# VoltageSourcePCB.net
KiCad netlist of a schematic drawn in EAGLE
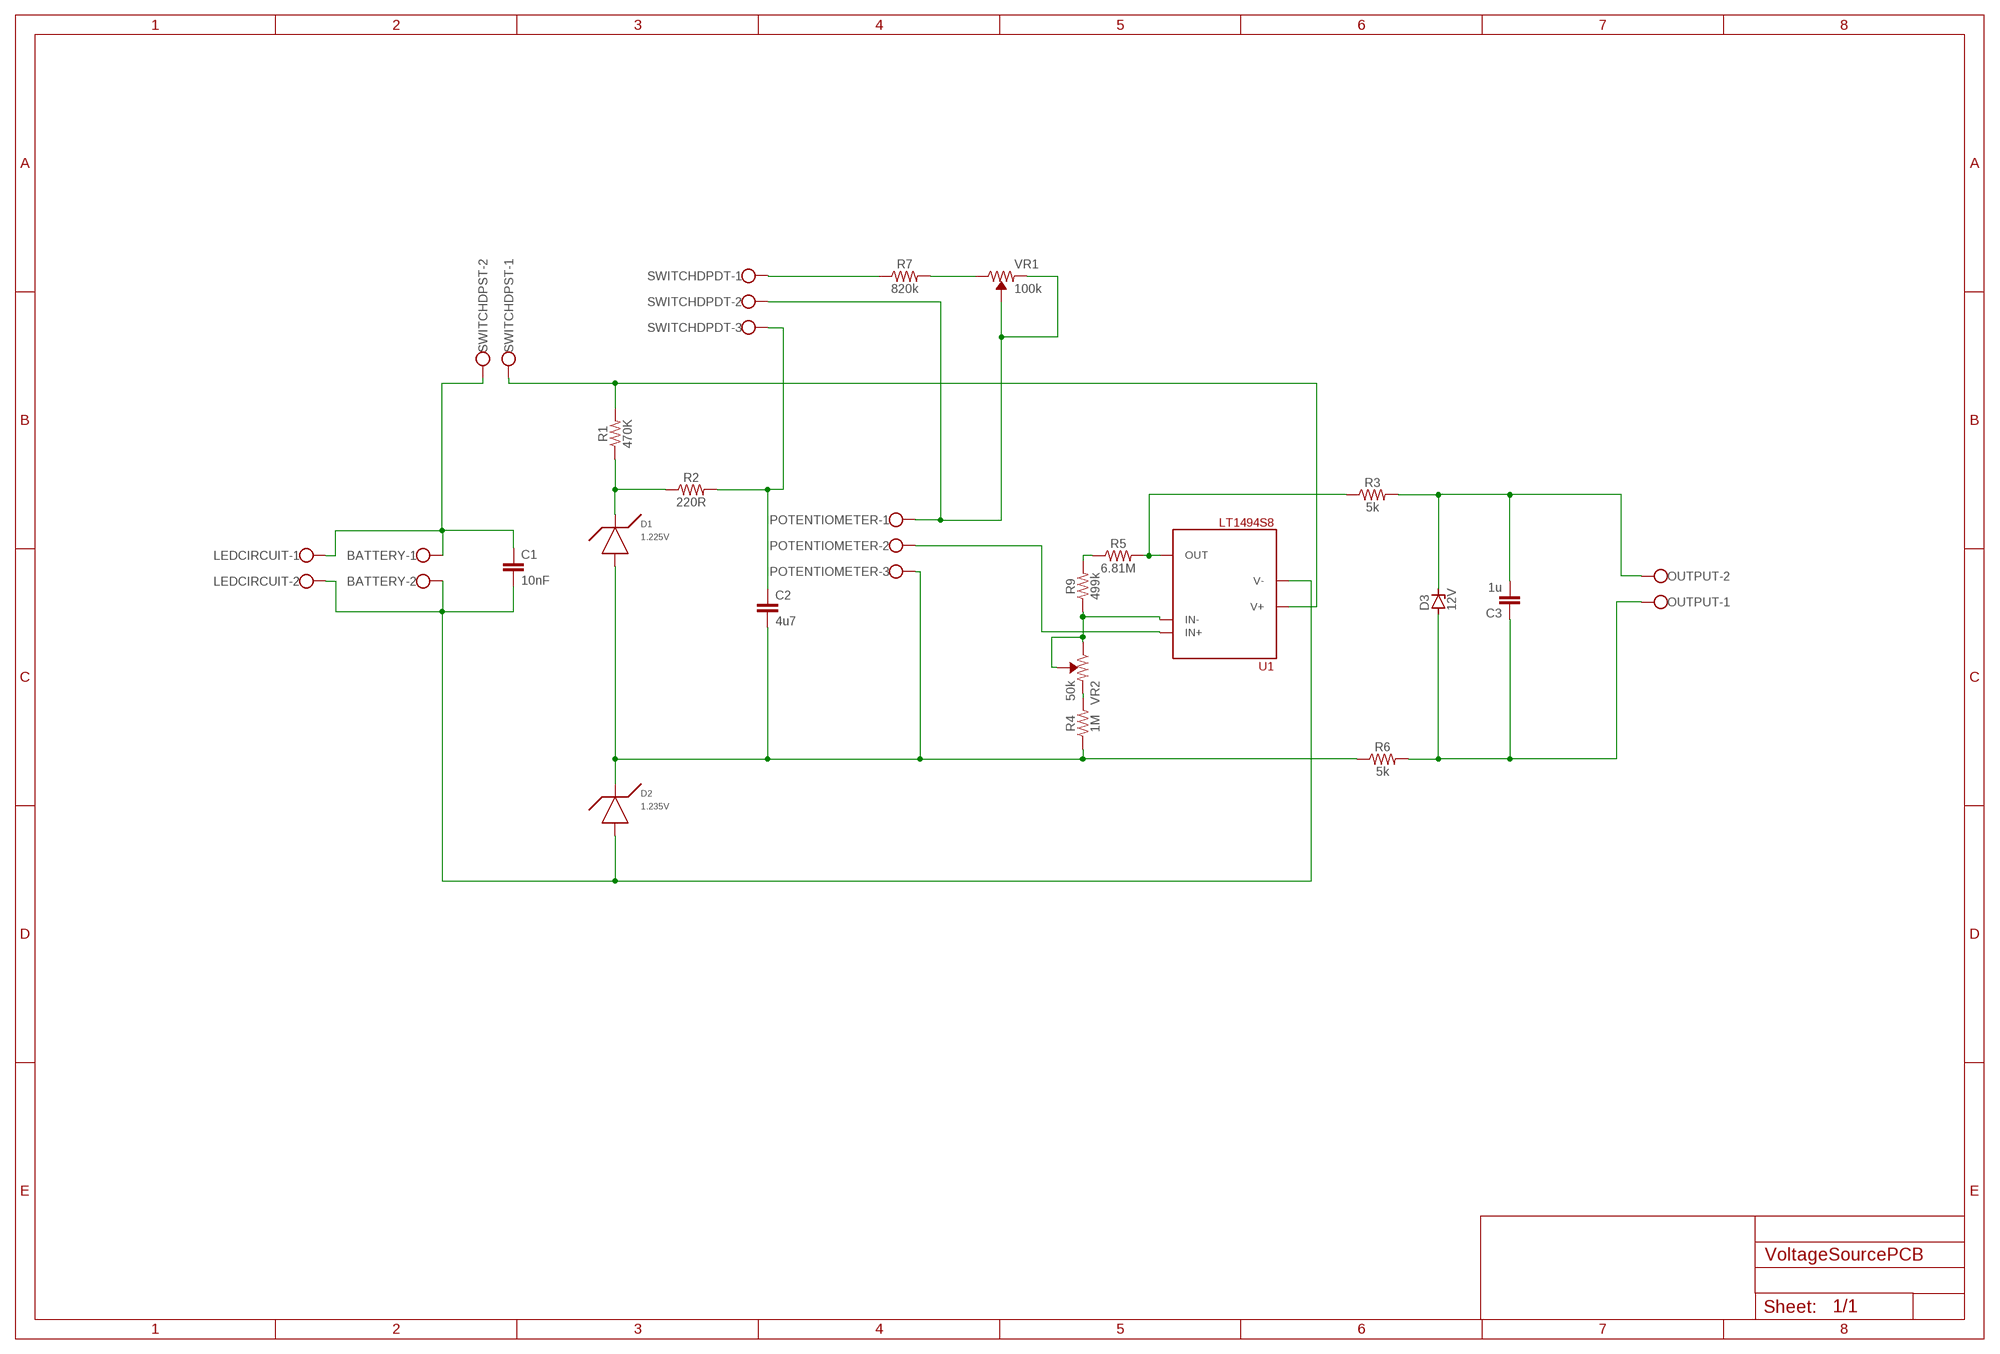
[diagram p0: schematic, sheet 1]

(export (version "E")
  (design (tool "Eeschema 10.0.6"))
  (components
    (comp (ref "BATTERY")
      (value "W237-102")
      (footprint "eagle-import:W237-102")
      (fields (field (name "MPN") "237-102"))
      (libsource (lib "eagle-import") (part "W237-102"))
    )
    (comp (ref "C1")
      (value "10nF")
      (footprint "eagle-import:C5B2.5")
      (libsource (lib "eagle-import") (part "C5/2.5"))
    )
    (comp (ref "C2")
      (value "4u7")
      (footprint "eagle-import:C22.5B11")
      (libsource (lib "eagle-import") (part "C22/11"))
    )
    (comp (ref "C3")
      (value "1u")
      (footprint "eagle-import:C150-072X183")
      (libsource (lib "eagle-import") (part "C-EU150-072X183"))
    )
    (comp (ref "D1")
      (value "1.225V")
      (footprint "eagle-import:LT1004CZ")
      (libsource (lib "eagle-import") (part "LT1004CZ1.225V"))
    )
    (comp (ref "D2")
      (value "1.235V")
      (footprint "eagle-import:LT1004CZ")
      (libsource (lib "eagle-import") (part "LT1004CZ1.235V"))
    )
    (comp (ref "D3")
      (value "12V")
      (footprint "eagle-import:C1702-15")
      (libsource (lib "eagle-import") (part "ZENER-DIODEC1702-15"))
    )
    (comp (ref "LEDCIRCUIT")
      (value "W237-102")
      (footprint "eagle-import:W237-102")
      (fields (field (name "MPN") "237-102"))
      (libsource (lib "eagle-import") (part "W237-102"))
    )
    (comp (ref "OUTPUT")
      (value "W237-102")
      (footprint "eagle-import:W237-102")
      (fields (field (name "MPN") "237-102"))
      (libsource (lib "eagle-import") (part "W237-102"))
    )
    (comp (ref "POTENTIOMETER")
      (value "W237-103")
      (footprint "eagle-import:W237-103")
      (fields (field (name "MPN") "237-103"))
      (libsource (lib "eagle-import") (part "W237-103"))
    )
    (comp (ref "R1")
      (value "470K")
      (footprint "eagle-import:0805")
      (libsource (lib "eagle-import") (part "RESISTOR0805"))
    )
    (comp (ref "R2")
      (value "220R")
      (footprint "eagle-import:0805")
      (libsource (lib "eagle-import") (part "RESISTOR0805"))
    )
    (comp (ref "R3")
      (value "5k")
      (footprint "eagle-import:0805")
      (libsource (lib "eagle-import") (part "RESISTOR0805"))
    )
    (comp (ref "R4")
      (value "1M")
      (footprint "eagle-import:0805")
      (libsource (lib "eagle-import") (part "RESISTOR0805"))
    )
    (comp (ref "R5")
      (value "6.81M")
      (footprint "eagle-import:0805")
      (libsource (lib "eagle-import") (part "RESISTOR0805"))
    )
    (comp (ref "R6")
      (value "5k")
      (footprint "eagle-import:0805")
      (libsource (lib "eagle-import") (part "RESISTOR0805"))
    )
    (comp (ref "R7")
      (value "820k")
      (footprint "eagle-import:0805")
      (libsource (lib "eagle-import") (part "RESISTOR0805"))
    )
    (comp (ref "R9")
      (value "499k")
      (footprint "eagle-import:0805")
      (libsource (lib "eagle-import") (part "RESISTOR0805"))
    )
    (comp (ref "SWITCHDPDT")
      (value "W237-103")
      (footprint "eagle-import:W237-103")
      (fields (field (name "MPN") "237-103"))
      (libsource (lib "eagle-import") (part "W237-103"))
    )
    (comp (ref "SWITCHDPST")
      (value "W237-102")
      (footprint "eagle-import:W237-102")
      (fields (field (name "MPN") "237-102"))
      (libsource (lib "eagle-import") (part "W237-102"))
    )
    (comp (ref "U1")
      (value "LT1494S8")
      (footprint "eagle-import:LT1494")
      (libsource (lib "eagle-import") (part "LT1494S8"))
    )
    (comp (ref "VR1")
      (value "100k")
      (footprint "eagle-import:TRIMPOT-SMD-TC33X")
      (libsource (lib "eagle-import") (part "TRIMPOT-SMD-3MM-OPEN-1/10W-25%"))
    )
    (comp (ref "VR2")
      (value "50k")
      (footprint "eagle-import:TRIMPOT-SMD-TC33X")
      (libsource (lib "eagle-import") (part "TRIMPOT-SMD-3MM-OPEN-1/10W-25%"))
    )
  )
  (nets
    (net (code "1") (name "Net-(BATTERYA-KL)") (class "Default")
      (node (ref "BATTERY") (pin "1") (pinfunction "KL_1") (pintype "passive"))
      (node (ref "C1") (pin "1") (pinfunction "1_1") (pintype "passive"))
    )
    (net (code "2") (name "Net-(BATTERYB-KL)") (class "Default")
      (node (ref "BATTERY") (pin "2") (pinfunction "KL_2") (pintype "passive"))
      (node (ref "C1") (pin "2") (pinfunction "2_2") (pintype "passive"))
    )
    (net (code "3") (name "Net-(D1-PadCATHODE)") (class "Default")
      (node (ref "D1") (pin "CATHODE") (pinfunction "CATHODE_CATHODE") (pintype "bidirectional"))
      (node (ref "R1") (pin "1") (pinfunction "1_1") (pintype "passive"))
      (node (ref "R2") (pin "1") (pinfunction "1_1") (pintype "passive"))
    )
    (net (code "4") (name "Net-(LEDCIRCUITA-KL)") (class "Default")
      (node (ref "LEDCIRCUIT") (pin "1") (pinfunction "KL_1") (pintype "passive"))
      (node (ref "SWITCHDPST") (pin "2") (pinfunction "KL_2") (pintype "passive"))
    )
    (net (code "5") (name "Net-(LEDCIRCUITB-KL)") (class "Default")
      (node (ref "D2") (pin "ANODE") (pinfunction "ANODE_ANODE") (pintype "bidirectional"))
      (node (ref "LEDCIRCUIT") (pin "2") (pinfunction "KL_2") (pintype "passive"))
      (node (ref "U1") (pin "4") (pinfunction "V-_4") (pintype "power_in"))
    )
    (net (code "6") (name "Net-(OUTPUTA-KL)") (class "Default")
      (node (ref "C3") (pin "1") (pinfunction "1_1") (pintype "passive"))
      (node (ref "D3") (pin "A") (pinfunction "A_A") (pintype "passive"))
      (node (ref "OUTPUT") (pin "1") (pinfunction "KL_1") (pintype "passive"))
      (node (ref "R6") (pin "2") (pinfunction "2_2") (pintype "passive"))
    )
    (net (code "7") (name "Net-(OUTPUTB-KL)") (class "Default")
      (node (ref "C3") (pin "2") (pinfunction "2_2") (pintype "passive"))
      (node (ref "D3") (pin "C") (pinfunction "C_C") (pintype "passive"))
      (node (ref "OUTPUT") (pin "2") (pinfunction "KL_2") (pintype "passive"))
      (node (ref "R3") (pin "2") (pinfunction "2_2") (pintype "passive"))
    )
    (net (code "8") (name "Net-(POTENTIOMETERA-KL)") (class "Default")
      (node (ref "POTENTIOMETER") (pin "1") (pinfunction "KL_1") (pintype "passive"))
      (node (ref "SWITCHDPDT") (pin "2") (pinfunction "KL_2") (pintype "passive"))
      (node (ref "VR1") (pin "2") (pinfunction "WIPER_2") (pintype "passive"))
      (node (ref "VR1") (pin "3") (pinfunction "CCW_3") (pintype "passive"))
    )
    (net (code "9") (name "Net-(POTENTIOMETERB-KL)") (class "Default")
      (node (ref "POTENTIOMETER") (pin "2") (pinfunction "KL_2") (pintype "passive"))
      (node (ref "U1") (pin "3") (pinfunction "IN+_3") (pintype "input"))
    )
    (net (code "10") (name "Net-(POTENTIOMETERC-KL)") (class "Default")
      (node (ref "C2") (pin "2") (pinfunction "2_2") (pintype "passive"))
      (node (ref "D1") (pin "ANODE") (pinfunction "ANODE_ANODE") (pintype "bidirectional"))
      (node (ref "D2") (pin "CATHODE") (pinfunction "CATHODE_CATHODE") (pintype "bidirectional"))
      (node (ref "POTENTIOMETER") (pin "3") (pinfunction "KL_3") (pintype "passive"))
      (node (ref "R4") (pin "1") (pinfunction "1_1") (pintype "passive"))
      (node (ref "R6") (pin "1") (pinfunction "1_1") (pintype "passive"))
    )
    (net (code "11") (name "Net-(R5-Pad1)") (class "Default")
      (node (ref "R5") (pin "1") (pinfunction "1_1") (pintype "passive"))
      (node (ref "R9") (pin "2") (pinfunction "2_2") (pintype "passive"))
    )
    (net (code "12") (name "Net-(SWITCHDPDTA-KL)") (class "Default")
      (node (ref "R7") (pin "1") (pinfunction "1_1") (pintype "passive"))
      (node (ref "SWITCHDPDT") (pin "1") (pinfunction "KL_1") (pintype "passive"))
    )
    (net (code "13") (name "Net-(SWITCHDPDTC-KL)") (class "Default")
      (node (ref "C2") (pin "1") (pinfunction "1_1") (pintype "passive"))
      (node (ref "R2") (pin "2") (pinfunction "2_2") (pintype "passive"))
      (node (ref "SWITCHDPDT") (pin "3") (pinfunction "KL_3") (pintype "passive"))
    )
    (net (code "14") (name "Net-(SWITCHDPSTA-KL)") (class "Default")
      (node (ref "R1") (pin "2") (pinfunction "2_2") (pintype "passive"))
      (node (ref "SWITCHDPST") (pin "1") (pinfunction "KL_1") (pintype "passive"))
      (node (ref "U1") (pin "7") (pinfunction "V+_7") (pintype "power_in"))
    )
    (net (code "15") (name "Net-(U1-IN-)") (class "Default")
      (node (ref "R9") (pin "1") (pinfunction "1_1") (pintype "passive"))
      (node (ref "U1") (pin "2") (pinfunction "IN-_2") (pintype "input"))
      (node (ref "VR2") (pin "1") (pinfunction "CW_1") (pintype "passive"))
      (node (ref "VR2") (pin "2") (pinfunction "WIPER_2") (pintype "passive"))
    )
    (net (code "16") (name "Net-(U1-OUT)") (class "Default")
      (node (ref "R3") (pin "1") (pinfunction "1_1") (pintype "passive"))
      (node (ref "R5") (pin "2") (pinfunction "2_2") (pintype "passive"))
      (node (ref "U1") (pin "6") (pinfunction "OUT_6") (pintype "output"))
    )
    (net (code "17") (name "Net-(VR1-CW)") (class "Default")
      (node (ref "R7") (pin "2") (pinfunction "2_2") (pintype "passive"))
      (node (ref "VR1") (pin "1") (pinfunction "CW_1") (pintype "passive"))
    )
    (net (code "18") (name "Net-(VR2-CCW)") (class "Default")
      (node (ref "R4") (pin "2") (pinfunction "2_2") (pintype "passive"))
      (node (ref "VR2") (pin "3") (pinfunction "CCW_3") (pintype "passive"))
    )
  )
)
